# ESP03_Adapter.net
KiCad netlist of a schematic drawn in EAGLE
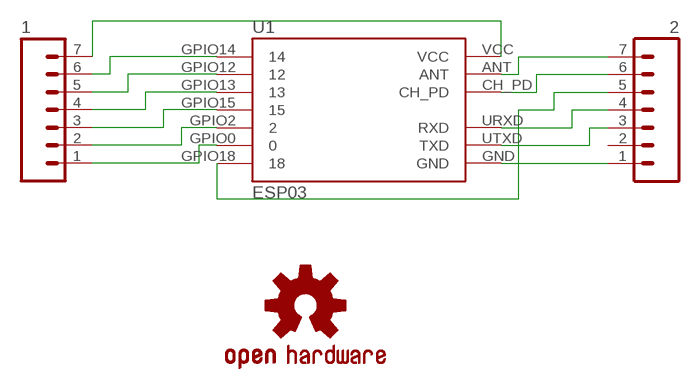
[diagram p0: schematic, sheet 1]

(export (version "E")
  (design (tool "Eeschema 10.0.6"))
  (components
    (comp (ref "1")
      (value "M07")
      (footprint "eagle-import:1X07")
      (libsource (lib "eagle-import") (part "M07"))
    )
    (comp (ref "2")
      (value "M07")
      (footprint "eagle-import:1X07")
      (libsource (lib "eagle-import") (part "M07"))
    )
    (comp (ref "LOGO1")
      (value "OSHW-LOGOM")
      (footprint "eagle-import:OSHW-LOGO-M")
      (libsource (lib "eagle-import") (part "OSHW-LOGOM"))
    )
    (comp (ref "U1")
      (value "ESP03")
      (footprint "eagle-import:ESP03")
      (libsource (lib "eagle-import") (part "ESP03"))
    )
  )
  (nets
    (net (code "1") (name "Net-(1-Pad7)") (class "Default")
      (node (ref "1") (pin "7") (pinfunction "7_7") (pintype "passive"))
      (node (ref "U1") (pin "VCC") (pinfunction "VCC_VCC") (pintype "power_in"))
    )
    (net (code "2") (name "Net-(2-Pad1)") (class "Default")
      (node (ref "2") (pin "1") (pinfunction "1_1") (pintype "passive"))
      (node (ref "U1") (pin "GND") (pinfunction "GND_GND") (pintype "power_in"))
    )
    (net (code "3") (name "Net-(2-Pad6)") (class "Default")
      (node (ref "2") (pin "6") (pinfunction "6_6") (pintype "passive"))
      (node (ref "U1") (pin "CH_PD") (pinfunction "CH_PD_CH_PD") (pintype "input"))
    )
    (net (code "4") (name "Net-(2-Pad7)") (class "Default")
      (node (ref "2") (pin "7") (pinfunction "7_7") (pintype "passive"))
      (node (ref "U1") (pin "ANT") (pinfunction "ANT_ANT") (pintype "bidirectional"))
    )
    (net (code "5") (name "Net-(U1-0)") (class "Default")
      (node (ref "1") (pin "1") (pinfunction "1_1") (pintype "passive"))
      (node (ref "U1") (pin "GPIO0") (pinfunction "0_GPIO0") (pintype "bidirectional"))
    )
    (net (code "6") (name "Net-(U1-2)") (class "Default")
      (node (ref "1") (pin "2") (pinfunction "2_2") (pintype "passive"))
      (node (ref "U1") (pin "GPIO2") (pinfunction "2_GPIO2") (pintype "bidirectional"))
    )
    (net (code "7") (name "Net-(U1-12)") (class "Default")
      (node (ref "1") (pin "5") (pinfunction "5_5") (pintype "passive"))
      (node (ref "U1") (pin "GPIO12") (pinfunction "12_GPIO12") (pintype "bidirectional"))
    )
    (net (code "8") (name "Net-(U1-13)") (class "Default")
      (node (ref "1") (pin "4") (pinfunction "4_4") (pintype "passive"))
      (node (ref "U1") (pin "GPIO13") (pinfunction "13_GPIO13") (pintype "bidirectional"))
    )
    (net (code "9") (name "Net-(U1-14)") (class "Default")
      (node (ref "1") (pin "6") (pinfunction "6_6") (pintype "passive"))
      (node (ref "U1") (pin "GPIO14") (pinfunction "14_GPIO14") (pintype "bidirectional"))
    )
    (net (code "10") (name "Net-(U1-15)") (class "Default")
      (node (ref "1") (pin "3") (pinfunction "3_3") (pintype "passive"))
      (node (ref "U1") (pin "GPIO15") (pinfunction "15_GPIO15") (pintype "bidirectional"))
    )
    (net (code "11") (name "Net-(U1-18)") (class "Default")
      (node (ref "2") (pin "5") (pinfunction "5_5") (pintype "passive"))
      (node (ref "U1") (pin "GPIO18") (pinfunction "18_GPIO18") (pintype "bidirectional"))
    )
    (net (code "12") (name "Net-(U1-RXD)") (class "Default")
      (node (ref "2") (pin "4") (pinfunction "4_4") (pintype "passive"))
      (node (ref "U1") (pin "URXD") (pinfunction "RXD_URXD") (pintype "output"))
    )
    (net (code "13") (name "Net-(U1-TXD)") (class "Default")
      (node (ref "2") (pin "3") (pinfunction "3_3") (pintype "passive"))
      (node (ref "U1") (pin "UTXD") (pinfunction "TXD_UTXD") (pintype "input"))
    )
    (net (code "14") (name "unconnected-(2-Pad2)") (class "Default")
      (node (ref "2") (pin "2") (pinfunction "2_2") (pintype "passive"))
    )
  )
)
